# LED_Chevron.net
KiCad netlist of a schematic drawn in EAGLE
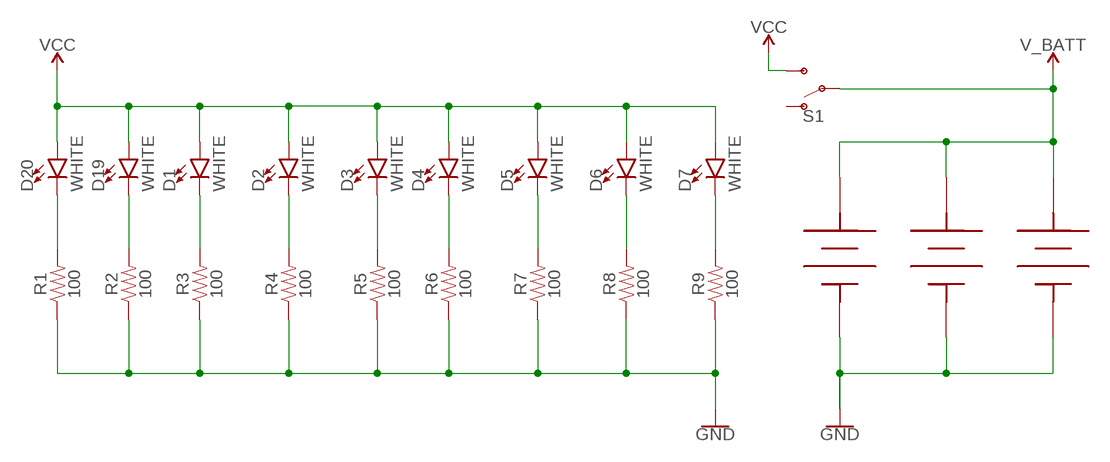
[diagram p0: schematic, sheet 1]

(export (version "E")
  (design (tool "Eeschema 10.0.6"))
  (components
    (comp (ref "D1")
      (value "WHITE")
      (footprint "eagle-import:LED-1206")
      (libsource (lib "eagle-import") (part "LED-WHITE1206"))
    )
    (comp (ref "D2")
      (value "WHITE")
      (footprint "eagle-import:LED-1206")
      (libsource (lib "eagle-import") (part "LED-WHITE1206"))
    )
    (comp (ref "D3")
      (value "WHITE")
      (footprint "eagle-import:LED-1206")
      (libsource (lib "eagle-import") (part "LED-WHITE1206"))
    )
    (comp (ref "D4")
      (value "WHITE")
      (footprint "eagle-import:LED-1206")
      (libsource (lib "eagle-import") (part "LED-WHITE1206"))
    )
    (comp (ref "D5")
      (value "WHITE")
      (footprint "eagle-import:LED-1206")
      (libsource (lib "eagle-import") (part "LED-WHITE1206"))
    )
    (comp (ref "D6")
      (value "WHITE")
      (footprint "eagle-import:LED-1206")
      (libsource (lib "eagle-import") (part "LED-WHITE1206"))
    )
    (comp (ref "D7")
      (value "WHITE")
      (footprint "eagle-import:LED-1206")
      (libsource (lib "eagle-import") (part "LED-WHITE1206"))
    )
    (comp (ref "D19")
      (value "WHITE")
      (footprint "eagle-import:LED-1206")
      (libsource (lib "eagle-import") (part "LED-WHITE1206"))
    )
    (comp (ref "D20")
      (value "WHITE")
      (footprint "eagle-import:LED-1206")
      (libsource (lib "eagle-import") (part "LED-WHITE1206"))
    )
    (comp (ref "R1")
      (value "100")
      (footprint "eagle-import:0603")
      (libsource (lib "eagle-import") (part "100OHM-0603-1/4W-5%"))
    )
    (comp (ref "R2")
      (value "100")
      (footprint "eagle-import:0603")
      (libsource (lib "eagle-import") (part "100OHM-0603-1/4W-5%"))
    )
    (comp (ref "R3")
      (value "100")
      (footprint "eagle-import:0603")
      (libsource (lib "eagle-import") (part "100OHM-0603-1/4W-5%"))
    )
    (comp (ref "R4")
      (value "100")
      (footprint "eagle-import:0603")
      (libsource (lib "eagle-import") (part "100OHM-0603-1/4W-5%"))
    )
    (comp (ref "R5")
      (value "100")
      (footprint "eagle-import:0603")
      (libsource (lib "eagle-import") (part "100OHM-0603-1/4W-5%"))
    )
    (comp (ref "R6")
      (value "100")
      (footprint "eagle-import:0603")
      (libsource (lib "eagle-import") (part "100OHM-0603-1/4W-5%"))
    )
    (comp (ref "R7")
      (value "100")
      (footprint "eagle-import:0603")
      (libsource (lib "eagle-import") (part "100OHM-0603-1/4W-5%"))
    )
    (comp (ref "R8")
      (value "100")
      (footprint "eagle-import:0603")
      (libsource (lib "eagle-import") (part "100OHM-0603-1/4W-5%"))
    )
    (comp (ref "R9")
      (value "100")
      (footprint "eagle-import:0603")
      (libsource (lib "eagle-import") (part "100OHM-0603-1/4W-5%"))
    )
    (comp (ref "S1")
      (value "SWITCH-SPDT-SMD-RIGHT-ANGLE")
      (footprint "eagle-import:SWITCH_SPST_SMD_A")
      (libsource (lib "eagle-import") (part "SWITCH-SPDT-SMD-RIGHT-ANGLE"))
    )
    (comp (ref "U$1")
      (value "7.8MM_COIN_CELL_BATTERY")
      (footprint "eagle-import:7.8MM_COIN_CELL_BATT")
      (fields (field (name "PARTNO") "36-2989-ND  "))
      (libsource (lib "eagle-import") (part "7.8MM_COIN_CELL_BATTERY"))
    )
    (comp (ref "U$2")
      (value "7.8MM_COIN_CELL_BATTERY")
      (footprint "eagle-import:7.8MM_COIN_CELL_BATT")
      (fields (field (name "PARTNO") "36-2989-ND  "))
      (libsource (lib "eagle-import") (part "7.8MM_COIN_CELL_BATTERY"))
    )
    (comp (ref "U$3")
      (value "7.8MM_COIN_CELL_BATTERY")
      (footprint "eagle-import:7.8MM_COIN_CELL_BATT")
      (fields (field (name "PARTNO") "36-2989-ND  "))
      (libsource (lib "eagle-import") (part "7.8MM_COIN_CELL_BATTERY"))
    )
  )
  (nets
    (net (code "1") (name "GND") (class "Default")
      (node (ref "R1") (pin "1") (pinfunction "1_1") (pintype "passive"))
      (node (ref "R2") (pin "1") (pinfunction "1_1") (pintype "passive"))
      (node (ref "R3") (pin "1") (pinfunction "1_1") (pintype "passive"))
      (node (ref "R4") (pin "1") (pinfunction "1_1") (pintype "passive"))
      (node (ref "R5") (pin "1") (pinfunction "1_1") (pintype "passive"))
      (node (ref "R6") (pin "1") (pinfunction "1_1") (pintype "passive"))
      (node (ref "R7") (pin "1") (pinfunction "1_1") (pintype "passive"))
      (node (ref "R8") (pin "1") (pinfunction "1_1") (pintype "passive"))
      (node (ref "R9") (pin "1") (pinfunction "1_1") (pintype "passive"))
      (node (ref "U$1") (pin "GND") (pinfunction "BATT-_GND") (pintype "input"))
      (node (ref "U$2") (pin "GND") (pinfunction "BATT-_GND") (pintype "input"))
      (node (ref "U$3") (pin "GND") (pinfunction "BATT-_GND") (pintype "input"))
    )
    (net (code "2") (name "Net-(D1-PadC)") (class "Default")
      (node (ref "D1") (pin "C") (pinfunction "C_C") (pintype "passive"))
      (node (ref "R3") (pin "2") (pinfunction "2_2") (pintype "passive"))
    )
    (net (code "3") (name "Net-(D2-PadC)") (class "Default")
      (node (ref "D2") (pin "C") (pinfunction "C_C") (pintype "passive"))
      (node (ref "R4") (pin "2") (pinfunction "2_2") (pintype "passive"))
    )
    (net (code "4") (name "Net-(D3-PadC)") (class "Default")
      (node (ref "D3") (pin "C") (pinfunction "C_C") (pintype "passive"))
      (node (ref "R5") (pin "2") (pinfunction "2_2") (pintype "passive"))
    )
    (net (code "5") (name "Net-(D4-PadC)") (class "Default")
      (node (ref "D4") (pin "C") (pinfunction "C_C") (pintype "passive"))
      (node (ref "R6") (pin "2") (pinfunction "2_2") (pintype "passive"))
    )
    (net (code "6") (name "Net-(D5-PadC)") (class "Default")
      (node (ref "D5") (pin "C") (pinfunction "C_C") (pintype "passive"))
      (node (ref "R7") (pin "2") (pinfunction "2_2") (pintype "passive"))
    )
    (net (code "7") (name "Net-(D6-PadC)") (class "Default")
      (node (ref "D6") (pin "C") (pinfunction "C_C") (pintype "passive"))
      (node (ref "R8") (pin "2") (pinfunction "2_2") (pintype "passive"))
    )
    (net (code "8") (name "Net-(D7-PadC)") (class "Default")
      (node (ref "D7") (pin "C") (pinfunction "C_C") (pintype "passive"))
      (node (ref "R9") (pin "2") (pinfunction "2_2") (pintype "passive"))
    )
    (net (code "9") (name "Net-(D19-PadC)") (class "Default")
      (node (ref "D19") (pin "C") (pinfunction "C_C") (pintype "passive"))
      (node (ref "R2") (pin "2") (pinfunction "2_2") (pintype "passive"))
    )
    (net (code "10") (name "Net-(D20-PadC)") (class "Default")
      (node (ref "D20") (pin "C") (pinfunction "C_C") (pintype "passive"))
      (node (ref "R1") (pin "2") (pinfunction "2_2") (pintype "passive"))
    )
    (net (code "11") (name "VCC") (class "Default")
      (node (ref "D1") (pin "A") (pinfunction "A_A") (pintype "passive"))
      (node (ref "D19") (pin "A") (pinfunction "A_A") (pintype "passive"))
      (node (ref "D2") (pin "A") (pinfunction "A_A") (pintype "passive"))
      (node (ref "D20") (pin "A") (pinfunction "A_A") (pintype "passive"))
      (node (ref "D3") (pin "A") (pinfunction "A_A") (pintype "passive"))
      (node (ref "D4") (pin "A") (pinfunction "A_A") (pintype "passive"))
      (node (ref "D5") (pin "A") (pinfunction "A_A") (pintype "passive"))
      (node (ref "D6") (pin "A") (pinfunction "A_A") (pintype "passive"))
      (node (ref "D7") (pin "A") (pinfunction "A_A") (pintype "passive"))
      (node (ref "S1") (pin "3") (pinfunction "S_3") (pintype "passive"))
    )
    (net (code "12") (name "V_BATT") (class "Default")
      (node (ref "S1") (pin "2") (pinfunction "P_2") (pintype "passive"))
      (node (ref "U$1") (pin "P$3") (pinfunction "BATT+_P$3") (pintype "input"))
      (node (ref "U$1") (pin "VBATT+") (pinfunction "BATT+_VBATT+") (pintype "input"))
      (node (ref "U$2") (pin "P$3") (pinfunction "BATT+_P$3") (pintype "input"))
      (node (ref "U$2") (pin "VBATT+") (pinfunction "BATT+_VBATT+") (pintype "input"))
      (node (ref "U$3") (pin "P$3") (pinfunction "BATT+_P$3") (pintype "input"))
      (node (ref "U$3") (pin "VBATT+") (pinfunction "BATT+_VBATT+") (pintype "input"))
    )
    (net (code "13") (name "unconnected-(S1-O-Pad1)") (class "Default")
      (node (ref "S1") (pin "1") (pinfunction "O_1") (pintype "passive"))
    )
  )
)
